# Ryan_and_Jimmy_Schematic_Attempt.net
KiCad netlist of a schematic drawn in EAGLE
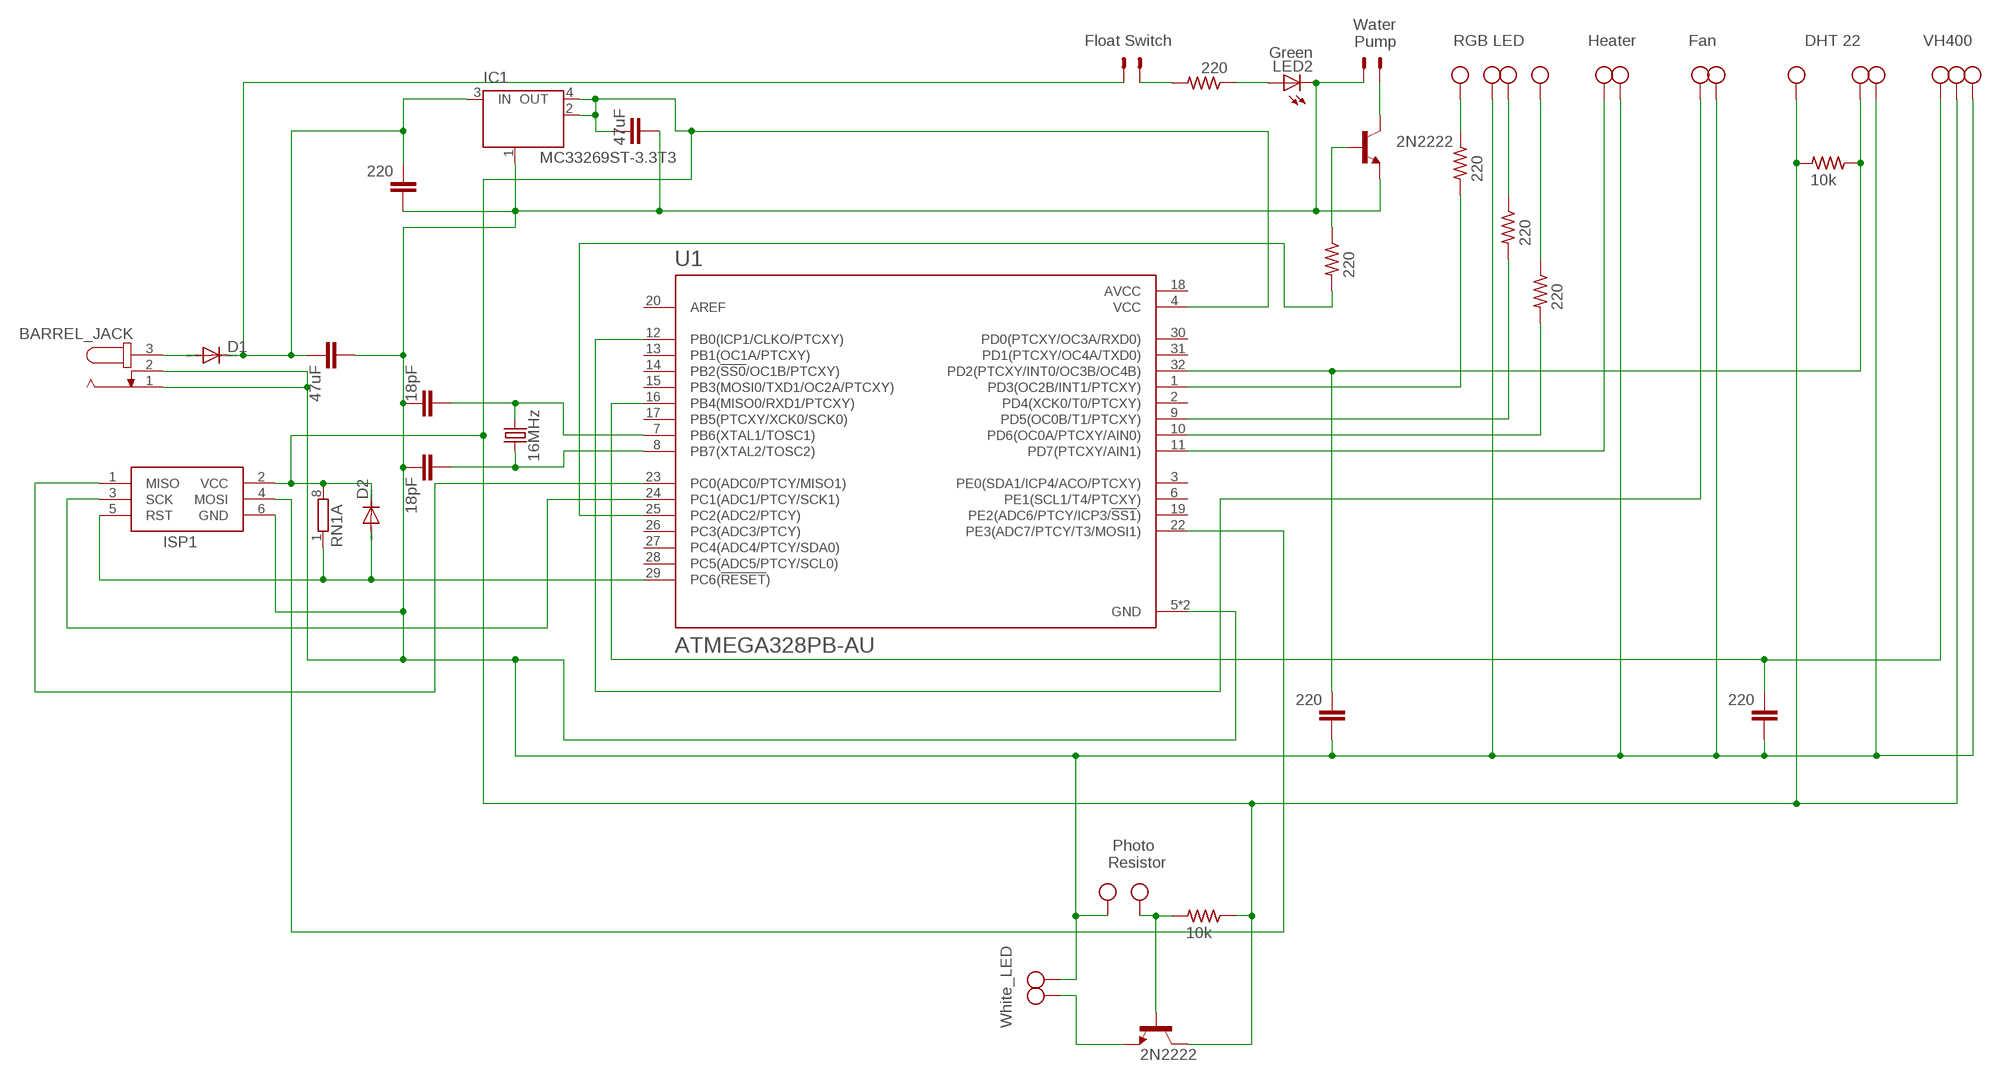
[diagram p0: schematic, sheet 1]

(export (version "E")
  (design (tool "Eeschema 10.0.6"))
  (components
    (comp (ref "BARREL_JACK")
      (value "JACK-PLUG1")
      (footprint "eagle-import:SPC4078")
      (libsource (lib "eagle-import") (part "JACK-PLUG1"))
    )
    (comp (ref "C1")
      (value "220")
      (footprint "eagle-import:C025-024X044")
      (libsource (lib "eagle-import") (part "C-EU025-024X044"))
    )
    (comp (ref "C3")
      (value "47uF")
      (footprint "eagle-import:C025-024X044")
      (libsource (lib "eagle-import") (part "C-EU025-024X044"))
    )
    (comp (ref "C6")
      (value "220")
      (footprint "eagle-import:C025-024X044")
      (libsource (lib "eagle-import") (part "C-EU025-024X044"))
    )
    (comp (ref "C8")
      (value "47uF")
      (footprint "eagle-import:C025-024X044")
      (libsource (lib "eagle-import") (part "C-EU025-024X044"))
    )
    (comp (ref "C9")
      (value "18pF")
      (footprint "eagle-import:C025-024X044")
      (libsource (lib "eagle-import") (part "C-EU025-024X044"))
    )
    (comp (ref "C11")
      (value "220")
      (footprint "eagle-import:C025-024X044")
      (libsource (lib "eagle-import") (part "C-EU025-024X044"))
    )
    (comp (ref "C12")
      (value "18pF")
      (footprint "eagle-import:C025-024X044")
      (libsource (lib "eagle-import") (part "C-EU025-024X044"))
    )
    (comp (ref "D1")
      (value "DIODE-DO214BA")
      (footprint "eagle-import:DO214BA")
      (libsource (lib "eagle-import") (part "DIODE-DO214BA"))
    )
    (comp (ref "D2")
      (value "DIODE-DO214BA")
      (footprint "eagle-import:DO214BA")
      (libsource (lib "eagle-import") (part "DIODE-DO214BA"))
    )
    (comp (ref "IC1")
      (value "MC33269ST-3.3T3")
      (footprint "eagle-import:SOT223")
      (libsource (lib "eagle-import") (part "MC33269ST-3.3T3"))
    )
    (comp (ref "ISP1")
      (value "AVRISP-6")
      (footprint "eagle-import:AVRISP")
      (libsource (lib "eagle-import") (part "AVRISP-6"))
    )
    (comp (ref "LED2")
      (value "Green")
      (footprint "eagle-import:CHIPLED_0805")
      (libsource (lib "eagle-import") (part "LEDCHIPLED_0805"))
    )
    (comp (ref "R1")
      (value "220")
      (footprint "eagle-import:R0805")
      (libsource (lib "eagle-import") (part "R-US_R0805"))
    )
    (comp (ref "R2")
      (value "220")
      (footprint "eagle-import:R0805")
      (libsource (lib "eagle-import") (part "R-US_R0805"))
    )
    (comp (ref "R3")
      (value "10k")
      (footprint "eagle-import:R0805")
      (libsource (lib "eagle-import") (part "R-US_R0805"))
    )
    (comp (ref "R4")
      (value "220")
      (footprint "eagle-import:R0805")
      (libsource (lib "eagle-import") (part "R-US_R0805"))
    )
    (comp (ref "R6")
      (value "220")
      (footprint "eagle-import:R0805")
      (libsource (lib "eagle-import") (part "R-US_R0805"))
    )
    (comp (ref "R7")
      (value "220")
      (footprint "eagle-import:R0805")
      (libsource (lib "eagle-import") (part "R-US_R0805"))
    )
    (comp (ref "R8")
      (value "10k")
      (footprint "eagle-import:R0805")
      (libsource (lib "eagle-import") (part "R-US_R0805"))
    )
    (comp (ref "RN1")
      (value "4R-NCAY16")
      (footprint "eagle-import:CAY16")
      (libsource (lib "eagle-import") (part "4R-NCAY16"))
    )
    (comp (ref "T1")
      (value "2N2222")
      (footprint "eagle-import:TO18")
      (libsource (lib "eagle-import") (part "2N2222"))
    )
    (comp (ref "T2")
      (value "2N2222")
      (footprint "eagle-import:TO18")
      (libsource (lib "eagle-import") (part "2N2222"))
    )
    (comp (ref "U1")
      (value "ATMEGA328PB-AU")
      (footprint "eagle-import:QFP80P900X900X120-32N")
      (fields (field (name "MF") "Microchip"))
      (libsource (lib "eagle-import") (part "ATMEGA328PB-AU"))
    )
    (comp (ref "X1")
      (value "1X03_5MM_SCREW")
      (footprint "eagle-import:W237-103")
      (fields (field (name "MPN") "237-103"))
      (libsource (lib "eagle-import") (part "1X03_5MM_SCREW"))
    )
    (comp (ref "X2")
      (value "1X02_5MM_SCREW")
      (footprint "eagle-import:W237-102")
      (fields (field (name "MPN") "237-102"))
      (libsource (lib "eagle-import") (part "1X02_5MM_SCREW"))
    )
    (comp (ref "X3")
      (value "1X03_5MM_SCREW")
      (footprint "eagle-import:W237-103")
      (fields (field (name "MPN") "237-103"))
      (libsource (lib "eagle-import") (part "1X03_5MM_SCREW"))
    )
    (comp (ref "X4")
      (value "1X02_5MM_SCREW")
      (footprint "eagle-import:W237-102")
      (fields (field (name "MPN") "237-102"))
      (libsource (lib "eagle-import") (part "1X02_5MM_SCREW"))
    )
    (comp (ref "X6")
      (value "1X02_5MM_SCREW")
      (footprint "eagle-import:W237-102")
      (fields (field (name "MPN") "237-102"))
      (libsource (lib "eagle-import") (part "1X02_5MM_SCREW"))
    )
    (comp (ref "X7")
      (value "W237-4")
      (footprint "eagle-import:W237-4")
      (libsource (lib "eagle-import") (part "W237-4"))
    )
    (comp (ref "X8")
      (value "1X02_5MM_SCREW")
      (footprint "eagle-import:W237-102")
      (fields (field (name "MPN") "237-102"))
      (libsource (lib "eagle-import") (part "1X02_5MM_SCREW"))
    )
    (comp (ref "X9")
      (value "332-02")
      (footprint "eagle-import:332-02")
      (libsource (lib "eagle-import") (part "332-02"))
    )
    (comp (ref "X10")
      (value "332-02")
      (footprint "eagle-import:332-02")
      (libsource (lib "eagle-import") (part "332-02"))
    )
    (comp (ref "Y1")
      (value "16MHz")
      (footprint "eagle-import:CRYSTAL-SMD-3.2X1.5MM")
      (libsource (lib "eagle-import") (part "CRYSTALSMD-3.2X1.5"))
    )
  )
  (nets
    (net (code "1") (name "/AVCC") (class "Default")
      (node (ref "U1") (pin "18") (pinfunction "AVCC_18") (pintype "power_in"))
    )
    (net (code "2") (name "Net-(BARREL_JACK-Pad3)") (class "Default")
      (node (ref "BARREL_JACK") (pin "3") (pinfunction "3_3") (pintype "passive"))
      (node (ref "D1") (pin "A") (pinfunction "A_A") (pintype "passive"))
    )
    (net (code "3") (name "Net-(IC1-GND{slash}ADJ)") (class "Default")
      (node (ref "BARREL_JACK") (pin "1") (pinfunction "1_1") (pintype "passive"))
      (node (ref "BARREL_JACK") (pin "2") (pinfunction "2_2") (pintype "passive"))
      (node (ref "C1") (pin "1") (pinfunction "1_1") (pintype "passive"))
      (node (ref "C11") (pin "1") (pinfunction "1_1") (pintype "passive"))
      (node (ref "C12") (pin "2") (pinfunction "2_2") (pintype "passive"))
      (node (ref "C3") (pin "1") (pinfunction "1_1") (pintype "passive"))
      (node (ref "C6") (pin "1") (pinfunction "1_1") (pintype "passive"))
      (node (ref "C8") (pin "1") (pinfunction "1_1") (pintype "passive"))
      (node (ref "C9") (pin "2") (pinfunction "2_2") (pintype "passive"))
      (node (ref "IC1") (pin "1") (pinfunction "GND/ADJ_1") (pintype "input"))
      (node (ref "ISP1") (pin "6") (pinfunction "GND_6") (pintype "power_in"))
      (node (ref "LED2") (pin "C") (pinfunction "C_C") (pintype "passive"))
      (node (ref "T1") (pin "1") (pinfunction "E_1") (pintype "passive"))
      (node (ref "U1") (pin "21") (pinfunction "GND_21") (pintype "power_in"))
      (node (ref "U1") (pin "5") (pinfunction "GND_5") (pintype "power_in"))
      (node (ref "X1") (pin "1") (pinfunction "KL_1") (pintype "passive"))
      (node (ref "X2") (pin "2") (pinfunction "KL_2") (pintype "passive"))
      (node (ref "X3") (pin "1") (pinfunction "KL_1") (pintype "passive"))
      (node (ref "X4") (pin "1") (pinfunction "KL_1") (pintype "passive"))
      (node (ref "X6") (pin "2") (pinfunction "KL_2") (pintype "passive"))
      (node (ref "X7") (pin "3") (pinfunction "KL_3") (pintype "passive"))
      (node (ref "X8") (pin "1") (pinfunction "KL_1") (pintype "passive"))
      (node (ref "X9") (pin "1") (pinfunction "S_1") (pintype "passive"))
    )
    (net (code "4") (name "Net-(IC1-IN)") (class "Default")
      (node (ref "C1") (pin "2") (pinfunction "2_2") (pintype "passive"))
      (node (ref "C8") (pin "2") (pinfunction "2_2") (pintype "passive"))
      (node (ref "D1") (pin "C") (pinfunction "C_C") (pintype "passive"))
      (node (ref "IC1") (pin "3") (pinfunction "IN_3") (pintype "input"))
      (node (ref "X10") (pin "2") (pinfunction "S_2") (pintype "passive"))
    )
    (net (code "5") (name "Net-(ISP1-MISO)") (class "Default")
      (node (ref "ISP1") (pin "1") (pinfunction "MISO_1") (pintype "input"))
      (node (ref "U1") (pin "23") (pinfunction "PC0(ADC0/PTCY/MISO1)_23") (pintype "bidirectional"))
    )
    (net (code "6") (name "Net-(ISP1-MOSI)") (class "Default")
      (node (ref "ISP1") (pin "4") (pinfunction "MOSI_4") (pintype "output"))
      (node (ref "U1") (pin "22") (pinfunction "PE3(ADC7/PTCY/T3/MOSI1)_22") (pintype "bidirectional"))
    )
    (net (code "7") (name "Net-(ISP1-RST)") (class "Default")
      (node (ref "D2") (pin "A") (pinfunction "A_A") (pintype "passive"))
      (node (ref "ISP1") (pin "5") (pinfunction "RST_5") (pintype "output"))
      (node (ref "RN1") (pin "1") (pinfunction "1_1") (pintype "passive"))
      (node (ref "U1") (pin "29") (pinfunction "PC6(~{RESET})_29") (pintype "bidirectional"))
    )
    (net (code "8") (name "Net-(ISP1-SCK)") (class "Default")
      (node (ref "ISP1") (pin "3") (pinfunction "SCK_3") (pintype "output"))
      (node (ref "U1") (pin "24") (pinfunction "PC1(ADC1/PTCY/SCK1)_24") (pintype "bidirectional"))
    )
    (net (code "9") (name "Net-(ISP1-VCC)") (class "Default")
      (node (ref "C3") (pin "2") (pinfunction "2_2") (pintype "passive"))
      (node (ref "D2") (pin "C") (pinfunction "C_C") (pintype "passive"))
      (node (ref "IC1") (pin "2") (pinfunction "OUT_2") (pintype "passive"))
      (node (ref "IC1") (pin "4") (pinfunction "OUT_4") (pintype "passive"))
      (node (ref "ISP1") (pin "2") (pinfunction "VCC_2") (pintype "power_in"))
      (node (ref "R3") (pin "1") (pinfunction "1_1") (pintype "passive"))
      (node (ref "R8") (pin "2") (pinfunction "2_2") (pintype "passive"))
      (node (ref "RN1") (pin "8") (pinfunction "2_8") (pintype "passive"))
      (node (ref "T2") (pin "3") (pinfunction "C_3") (pintype "passive"))
      (node (ref "U1") (pin "4") (pinfunction "VCC_4") (pintype "power_in"))
      (node (ref "X1") (pin "3") (pinfunction "KL_3") (pintype "passive"))
      (node (ref "X3") (pin "2") (pinfunction "KL_2") (pintype "passive"))
    )
    (net (code "10") (name "Net-(LED2-PadA)") (class "Default")
      (node (ref "LED2") (pin "A") (pinfunction "A_A") (pintype "passive"))
      (node (ref "R1") (pin "1") (pinfunction "1_1") (pintype "passive"))
    )
    (net (code "11") (name "Net-(T1-B)") (class "Default")
      (node (ref "R4") (pin "1") (pinfunction "1_1") (pintype "passive"))
      (node (ref "T1") (pin "2") (pinfunction "B_2") (pintype "passive"))
    )
    (net (code "12") (name "Net-(T1-C)") (class "Default")
      (node (ref "T1") (pin "3") (pinfunction "C_3") (pintype "passive"))
      (node (ref "X9") (pin "2") (pinfunction "S_2") (pintype "passive"))
    )
    (net (code "13") (name "Net-(T2-B)") (class "Default")
      (node (ref "R3") (pin "2") (pinfunction "2_2") (pintype "passive"))
      (node (ref "T2") (pin "2") (pinfunction "B_2") (pintype "passive"))
      (node (ref "X2") (pin "1") (pinfunction "KL_1") (pintype "passive"))
    )
    (net (code "14") (name "Net-(T2-E)") (class "Default")
      (node (ref "T2") (pin "1") (pinfunction "E_1") (pintype "passive"))
      (node (ref "X6") (pin "1") (pinfunction "KL_1") (pintype "passive"))
    )
    (net (code "15") (name "Net-(U1-PB0(ICP1{slash}CLKO{slash}PTCXY))") (class "Default")
      (node (ref "U1") (pin "12") (pinfunction "PB0(ICP1/CLKO/PTCXY)_12") (pintype "bidirectional"))
      (node (ref "X8") (pin "2") (pinfunction "KL_2") (pintype "passive"))
    )
    (net (code "16") (name "Net-(U1-PB4(MISO0{slash}RXD1{slash}PTCXY))") (class "Default")
      (node (ref "C11") (pin "2") (pinfunction "2_2") (pintype "passive"))
      (node (ref "U1") (pin "16") (pinfunction "PB4(MISO0/RXD1/PTCXY)_16") (pintype "bidirectional"))
      (node (ref "X3") (pin "3") (pinfunction "KL_3") (pintype "passive"))
    )
    (net (code "17") (name "Net-(U1-PB6(XTAL1{slash}TOSC1))") (class "Default")
      (node (ref "C9") (pin "1") (pinfunction "1_1") (pintype "passive"))
      (node (ref "U1") (pin "7") (pinfunction "PB6(XTAL1/TOSC1)_7") (pintype "bidirectional"))
      (node (ref "Y1") (pin "P$2") (pinfunction "2_P$2") (pintype "passive"))
    )
    (net (code "18") (name "Net-(U1-PB7(XTAL2{slash}TOSC2))") (class "Default")
      (node (ref "C12") (pin "1") (pinfunction "1_1") (pintype "passive"))
      (node (ref "U1") (pin "8") (pinfunction "PB7(XTAL2/TOSC2)_8") (pintype "bidirectional"))
      (node (ref "Y1") (pin "P$1") (pinfunction "1_P$1") (pintype "passive"))
    )
    (net (code "19") (name "Net-(U1-PC2(ADC2{slash}PTCY))") (class "Default")
      (node (ref "R4") (pin "2") (pinfunction "2_2") (pintype "passive"))
      (node (ref "U1") (pin "25") (pinfunction "PC2(ADC2/PTCY)_25") (pintype "bidirectional"))
    )
    (net (code "20") (name "Net-(U1-PD2(PTCXY{slash}INT0{slash}OC3B{slash}OC4B))") (class "Default")
      (node (ref "C6") (pin "2") (pinfunction "2_2") (pintype "passive"))
      (node (ref "R8") (pin "1") (pinfunction "1_1") (pintype "passive"))
      (node (ref "U1") (pin "32") (pinfunction "PD2(PTCXY/INT0/OC3B/OC4B)_32") (pintype "bidirectional"))
      (node (ref "X1") (pin "2") (pinfunction "KL_2") (pintype "passive"))
    )
    (net (code "21") (name "Net-(U1-PD3(OC2B{slash}INT1{slash}PTCXY))") (class "Default")
      (node (ref "R2") (pin "2") (pinfunction "2_2") (pintype "passive"))
      (node (ref "U1") (pin "1") (pinfunction "PD3(OC2B/INT1/PTCXY)_1") (pintype "bidirectional"))
    )
    (net (code "22") (name "Net-(U1-PD5(OC0B{slash}T1{slash}PTCXY))") (class "Default")
      (node (ref "R6") (pin "2") (pinfunction "2_2") (pintype "passive"))
      (node (ref "U1") (pin "9") (pinfunction "PD5(OC0B/T1/PTCXY)_9") (pintype "bidirectional"))
    )
    (net (code "23") (name "Net-(U1-PD6(OC0A{slash}PTCXY{slash}AIN0))") (class "Default")
      (node (ref "R7") (pin "2") (pinfunction "2_2") (pintype "passive"))
      (node (ref "U1") (pin "10") (pinfunction "PD6(OC0A/PTCXY/AIN0)_10") (pintype "bidirectional"))
    )
    (net (code "24") (name "Net-(U1-PD7(PTCXY{slash}AIN1))") (class "Default")
      (node (ref "U1") (pin "11") (pinfunction "PD7(PTCXY/AIN1)_11") (pintype "bidirectional"))
      (node (ref "X4") (pin "2") (pinfunction "KL_2") (pintype "passive"))
    )
    (net (code "25") (name "Net-(X7A-KL)") (class "Default")
      (node (ref "R7") (pin "1") (pinfunction "1_1") (pintype "passive"))
      (node (ref "X7") (pin "1") (pinfunction "KL_1") (pintype "passive"))
    )
    (net (code "26") (name "Net-(X7B-KL)") (class "Default")
      (node (ref "R6") (pin "1") (pinfunction "1_1") (pintype "passive"))
      (node (ref "X7") (pin "2") (pinfunction "KL_2") (pintype "passive"))
    )
    (net (code "27") (name "Net-(X7D-KL)") (class "Default")
      (node (ref "R2") (pin "1") (pinfunction "1_1") (pintype "passive"))
      (node (ref "X7") (pin "4") (pinfunction "KL_4") (pintype "passive"))
    )
    (net (code "28") (name "Net-(X10A-S)") (class "Default")
      (node (ref "R1") (pin "2") (pinfunction "2_2") (pintype "passive"))
      (node (ref "X10") (pin "1") (pinfunction "S_1") (pintype "passive"))
    )
    (net (code "29") (name "unconnected-(U1-AREF-Pad20)") (class "Default")
      (node (ref "U1") (pin "20") (pinfunction "AREF_20") (pintype "input"))
    )
    (net (code "30") (name "unconnected-(U1-PB1(OC1A{slash}PTCXY)-Pad13)") (class "Default")
      (node (ref "U1") (pin "13") (pinfunction "PB1(OC1A/PTCXY)_13") (pintype "bidirectional"))
    )
    (net (code "31") (name "unconnected-(U1-PB2(~{SS0}{slash}OC1B{slash}PTCXY)-Pad14)") (class "Default")
      (node (ref "U1") (pin "14") (pinfunction "PB2(~{SS0}/OC1B/PTCXY)_14") (pintype "bidirectional"))
    )
    (net (code "32") (name "unconnected-(U1-PB3(MOSI0{slash}TXD1{slash}OC2A{slash}PTCXY)-Pad15)") (class "Default")
      (node (ref "U1") (pin "15") (pinfunction "PB3(MOSI0/TXD1/OC2A/PTCXY)_15") (pintype "bidirectional"))
    )
    (net (code "33") (name "unconnected-(U1-PB5(PTCXY{slash}XCK0{slash}SCK0)-Pad17)") (class "Default")
      (node (ref "U1") (pin "17") (pinfunction "PB5(PTCXY/XCK0/SCK0)_17") (pintype "bidirectional"))
    )
    (net (code "34") (name "unconnected-(U1-PC3(ADC3{slash}PTCY)-Pad26)") (class "Default")
      (node (ref "U1") (pin "26") (pinfunction "PC3(ADC3/PTCY)_26") (pintype "bidirectional"))
    )
    (net (code "35") (name "unconnected-(U1-PC4(ADC4{slash}PTCY{slash}SDA0)-Pad27)") (class "Default")
      (node (ref "U1") (pin "27") (pinfunction "PC4(ADC4/PTCY/SDA0)_27") (pintype "bidirectional"))
    )
    (net (code "36") (name "unconnected-(U1-PC5(ADC5{slash}PTCY{slash}SCL0)-Pad28)") (class "Default")
      (node (ref "U1") (pin "28") (pinfunction "PC5(ADC5/PTCY/SCL0)_28") (pintype "bidirectional"))
    )
    (net (code "37") (name "unconnected-(U1-PD0(PTCXY{slash}OC3A{slash}RXD0)-Pad30)") (class "Default")
      (node (ref "U1") (pin "30") (pinfunction "PD0(PTCXY/OC3A/RXD0)_30") (pintype "bidirectional"))
    )
    (net (code "38") (name "unconnected-(U1-PD1(PTCXY{slash}OC4A{slash}TXD0)-Pad31)") (class "Default")
      (node (ref "U1") (pin "31") (pinfunction "PD1(PTCXY/OC4A/TXD0)_31") (pintype "bidirectional"))
    )
    (net (code "39") (name "unconnected-(U1-PD4(XCK0{slash}T0{slash}PTCXY)-Pad2)") (class "Default")
      (node (ref "U1") (pin "2") (pinfunction "PD4(XCK0/T0/PTCXY)_2") (pintype "bidirectional"))
    )
    (net (code "40") (name "unconnected-(U1-PE0(SDA1{slash}ICP4{slash}ACO{slash}PTCXY)-Pad3)") (class "Default")
      (node (ref "U1") (pin "3") (pinfunction "PE0(SDA1/ICP4/ACO/PTCXY)_3") (pintype "bidirectional"))
    )
    (net (code "41") (name "unconnected-(U1-PE1(SCL1{slash}T4{slash}PTCXY)-Pad6)") (class "Default")
      (node (ref "U1") (pin "6") (pinfunction "PE1(SCL1/T4/PTCXY)_6") (pintype "bidirectional"))
    )
    (net (code "42") (name "unconnected-(U1-PE2(ADC6{slash}PTCY{slash}ICP3{slash}~{SS1})-Pad19)") (class "Default")
      (node (ref "U1") (pin "19") (pinfunction "PE2(ADC6/PTCY/ICP3/~{SS1})_19") (pintype "bidirectional"))
    )
  )
)
